# G853X.net
KiCad netlist of a schematic drawn in EAGLE
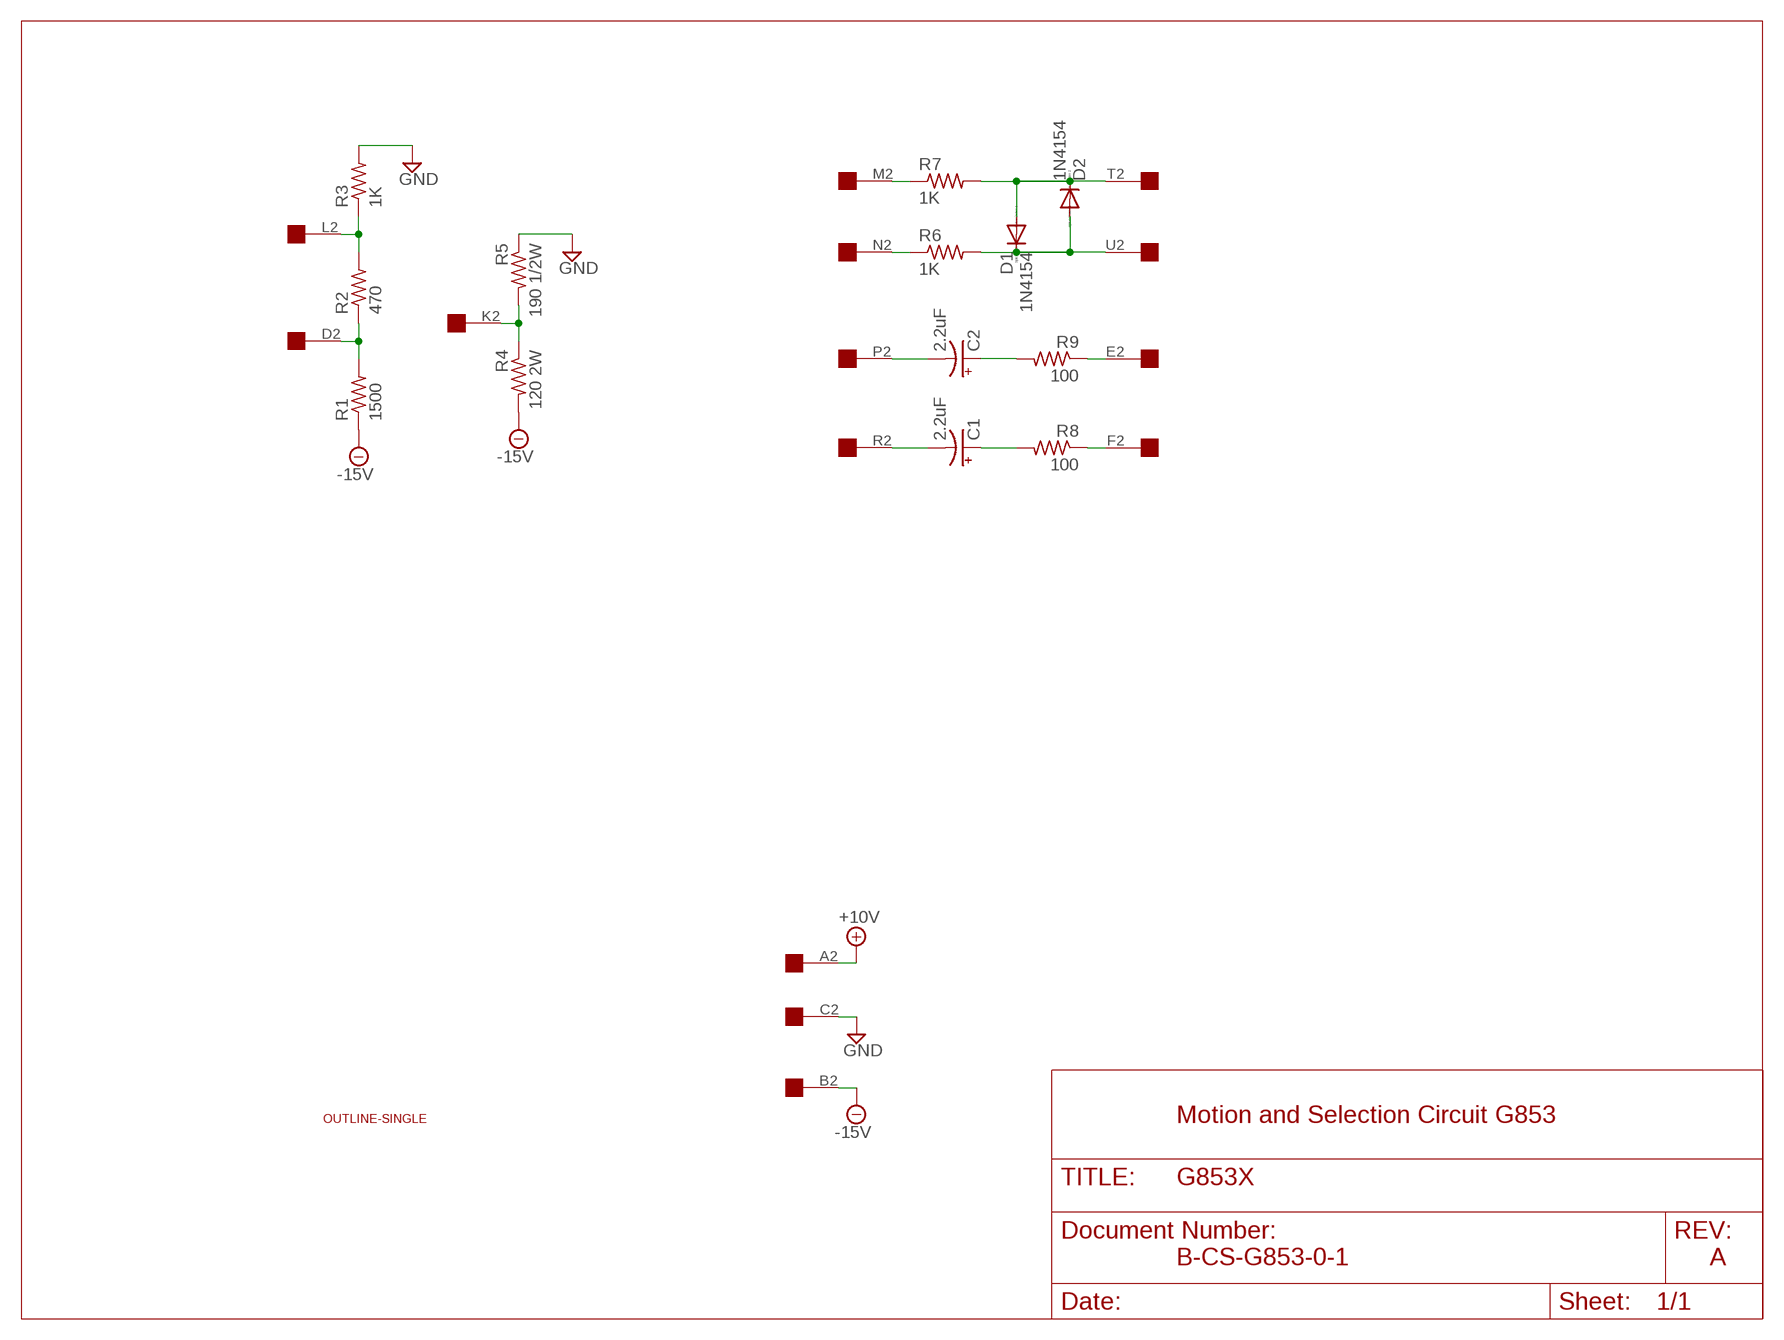
[diagram p0: schematic, sheet 1]

(export (version "E")
  (design (tool "Eeschema 10.0.6"))
  (components
    (comp (ref "C1")
      (value "2.2uF")
      (footprint "eagle-import:E15-5")
      (libsource (lib "eagle-import") (part "CPOL-USE15-5AXIAL"))
    )
    (comp (ref "C2")
      (value "2.2uF")
      (footprint "eagle-import:E15-5")
      (libsource (lib "eagle-import") (part "CPOL-USE15-5AXIAL"))
    )
    (comp (ref "D1")
      (value "1N4154")
      (footprint "eagle-import:DO35-10")
      (libsource (lib "eagle-import") (part "1N4148DO35-10"))
    )
    (comp (ref "D2")
      (value "1N4154")
      (footprint "eagle-import:DO35-10")
      (libsource (lib "eagle-import") (part "1N4148DO35-10"))
    )
    (comp (ref "R1")
      (value "1500")
      (footprint "eagle-import:0207_10")
      (libsource (lib "eagle-import") (part "R-US_0207/10"))
    )
    (comp (ref "R2")
      (value "470")
      (footprint "eagle-import:0207_10")
      (libsource (lib "eagle-import") (part "R-US_0207/10"))
    )
    (comp (ref "R3")
      (value "1K")
      (footprint "eagle-import:0207_10")
      (libsource (lib "eagle-import") (part "R-US_0207/10"))
    )
    (comp (ref "R4")
      (value "120 2W")
      (footprint "eagle-import:P0817_22")
      (libsource (lib "eagle-import") (part "R-US_0817/22"))
    )
    (comp (ref "R5")
      (value "190 1/2W")
      (footprint "eagle-import:0309_12")
      (libsource (lib "eagle-import") (part "R-US_0309/12"))
    )
    (comp (ref "R6")
      (value "1K")
      (footprint "eagle-import:0207_10")
      (libsource (lib "eagle-import") (part "R-US_0207/10"))
    )
    (comp (ref "R7")
      (value "1K")
      (footprint "eagle-import:0207_10")
      (libsource (lib "eagle-import") (part "R-US_0207/10"))
    )
    (comp (ref "R8")
      (value "100")
      (footprint "eagle-import:0207_10")
      (libsource (lib "eagle-import") (part "R-US_0207/10"))
    )
    (comp (ref "R9")
      (value "100")
      (footprint "eagle-import:0207_10")
      (libsource (lib "eagle-import") (part "R-US_0207/10"))
    )
    (comp (ref "U$1")
      (value "OUTLINE-SINGLE")
      (footprint "eagle-import:SINGLE")
      (libsource (lib "eagle-import") (part "OUTLINE-SINGLE"))
    )
    (comp (ref "U$2")
      (value "EDGE-1")
      (footprint "eagle-import:EDGE-CON1")
      (libsource (lib "eagle-import") (part "EDGE-1"))
    )
  )
  (nets
    (net (code "1") (name "+10V") (class "Default")
      (node (ref "U$2") (pin "A2") (pinfunction "1_A2") (pintype "bidirectional"))
    )
    (net (code "2") (name "-15V") (class "Default")
      (node (ref "R1") (pin "1") (pinfunction "1_1") (pintype "passive"))
      (node (ref "R4") (pin "2") (pinfunction "2_2") (pintype "passive"))
      (node (ref "U$2") (pin "B2") (pinfunction "1_B2") (pintype "bidirectional"))
    )
    (net (code "3") (name "GND") (class "Default")
      (node (ref "R3") (pin "2") (pinfunction "2_2") (pintype "passive"))
      (node (ref "R5") (pin "1") (pinfunction "1_1") (pintype "passive"))
      (node (ref "U$2") (pin "C2") (pinfunction "1_C2") (pintype "bidirectional"))
    )
    (net (code "4") (name "Net-(C1-Pad+)") (class "Default")
      (node (ref "C1") (pin "+") (pinfunction "+_+") (pintype "passive"))
      (node (ref "R8") (pin "2") (pinfunction "2_2") (pintype "passive"))
    )
    (net (code "5") (name "Net-(C2-Pad+)") (class "Default")
      (node (ref "C2") (pin "+") (pinfunction "+_+") (pintype "passive"))
      (node (ref "R9") (pin "2") (pinfunction "2_2") (pintype "passive"))
    )
    (net (code "6") (name "Net-(U$2D-1)") (class "Default")
      (node (ref "R1") (pin "2") (pinfunction "2_2") (pintype "passive"))
      (node (ref "R2") (pin "1") (pinfunction "1_1") (pintype "passive"))
      (node (ref "U$2") (pin "D2") (pinfunction "1_D2") (pintype "bidirectional"))
    )
    (net (code "7") (name "Net-(U$2E-1)") (class "Default")
      (node (ref "R9") (pin "1") (pinfunction "1_1") (pintype "passive"))
      (node (ref "U$2") (pin "E2") (pinfunction "1_E2") (pintype "bidirectional"))
    )
    (net (code "8") (name "Net-(U$2F-1)") (class "Default")
      (node (ref "R8") (pin "1") (pinfunction "1_1") (pintype "passive"))
      (node (ref "U$2") (pin "F2") (pinfunction "1_F2") (pintype "bidirectional"))
    )
    (net (code "9") (name "Net-(U$2I-1)") (class "Default")
      (node (ref "R4") (pin "1") (pinfunction "1_1") (pintype "passive"))
      (node (ref "R5") (pin "2") (pinfunction "2_2") (pintype "passive"))
      (node (ref "U$2") (pin "K2") (pinfunction "1_K2") (pintype "bidirectional"))
    )
    (net (code "10") (name "Net-(U$2J-1)") (class "Default")
      (node (ref "R2") (pin "2") (pinfunction "2_2") (pintype "passive"))
      (node (ref "R3") (pin "1") (pinfunction "1_1") (pintype "passive"))
      (node (ref "U$2") (pin "L2") (pinfunction "1_L2") (pintype "bidirectional"))
    )
    (net (code "11") (name "Net-(U$2K-1)") (class "Default")
      (node (ref "R7") (pin "1") (pinfunction "1_1") (pintype "passive"))
      (node (ref "U$2") (pin "M2") (pinfunction "1_M2") (pintype "bidirectional"))
    )
    (net (code "12") (name "Net-(U$2L-1)") (class "Default")
      (node (ref "R6") (pin "1") (pinfunction "1_1") (pintype "passive"))
      (node (ref "U$2") (pin "N2") (pinfunction "1_N2") (pintype "bidirectional"))
    )
    (net (code "13") (name "Net-(U$2M-1)") (class "Default")
      (node (ref "C2") (pin "-") (pinfunction "-_-") (pintype "passive"))
      (node (ref "U$2") (pin "P2") (pinfunction "1_P2") (pintype "bidirectional"))
    )
    (net (code "14") (name "Net-(U$2N-1)") (class "Default")
      (node (ref "C1") (pin "-") (pinfunction "-_-") (pintype "passive"))
      (node (ref "U$2") (pin "R2") (pinfunction "1_R2") (pintype "bidirectional"))
    )
    (net (code "15") (name "Net-(U$2P-1)") (class "Default")
      (node (ref "D1") (pin "A") (pinfunction "A_A") (pintype "passive"))
      (node (ref "D2") (pin "C") (pinfunction "C_C") (pintype "passive"))
      (node (ref "R7") (pin "2") (pinfunction "2_2") (pintype "passive"))
      (node (ref "U$2") (pin "T2") (pinfunction "1_T2") (pintype "bidirectional"))
    )
    (net (code "16") (name "Net-(U$2Q-1)") (class "Default")
      (node (ref "D1") (pin "C") (pinfunction "C_C") (pintype "passive"))
      (node (ref "D2") (pin "A") (pinfunction "A_A") (pintype "passive"))
      (node (ref "R6") (pin "2") (pinfunction "2_2") (pintype "passive"))
      (node (ref "U$2") (pin "U2") (pinfunction "1_U2") (pintype "bidirectional"))
    )
  )
)
